# 464421_22-01_Power.net
KiCad netlist of a schematic drawn in Altium Designer
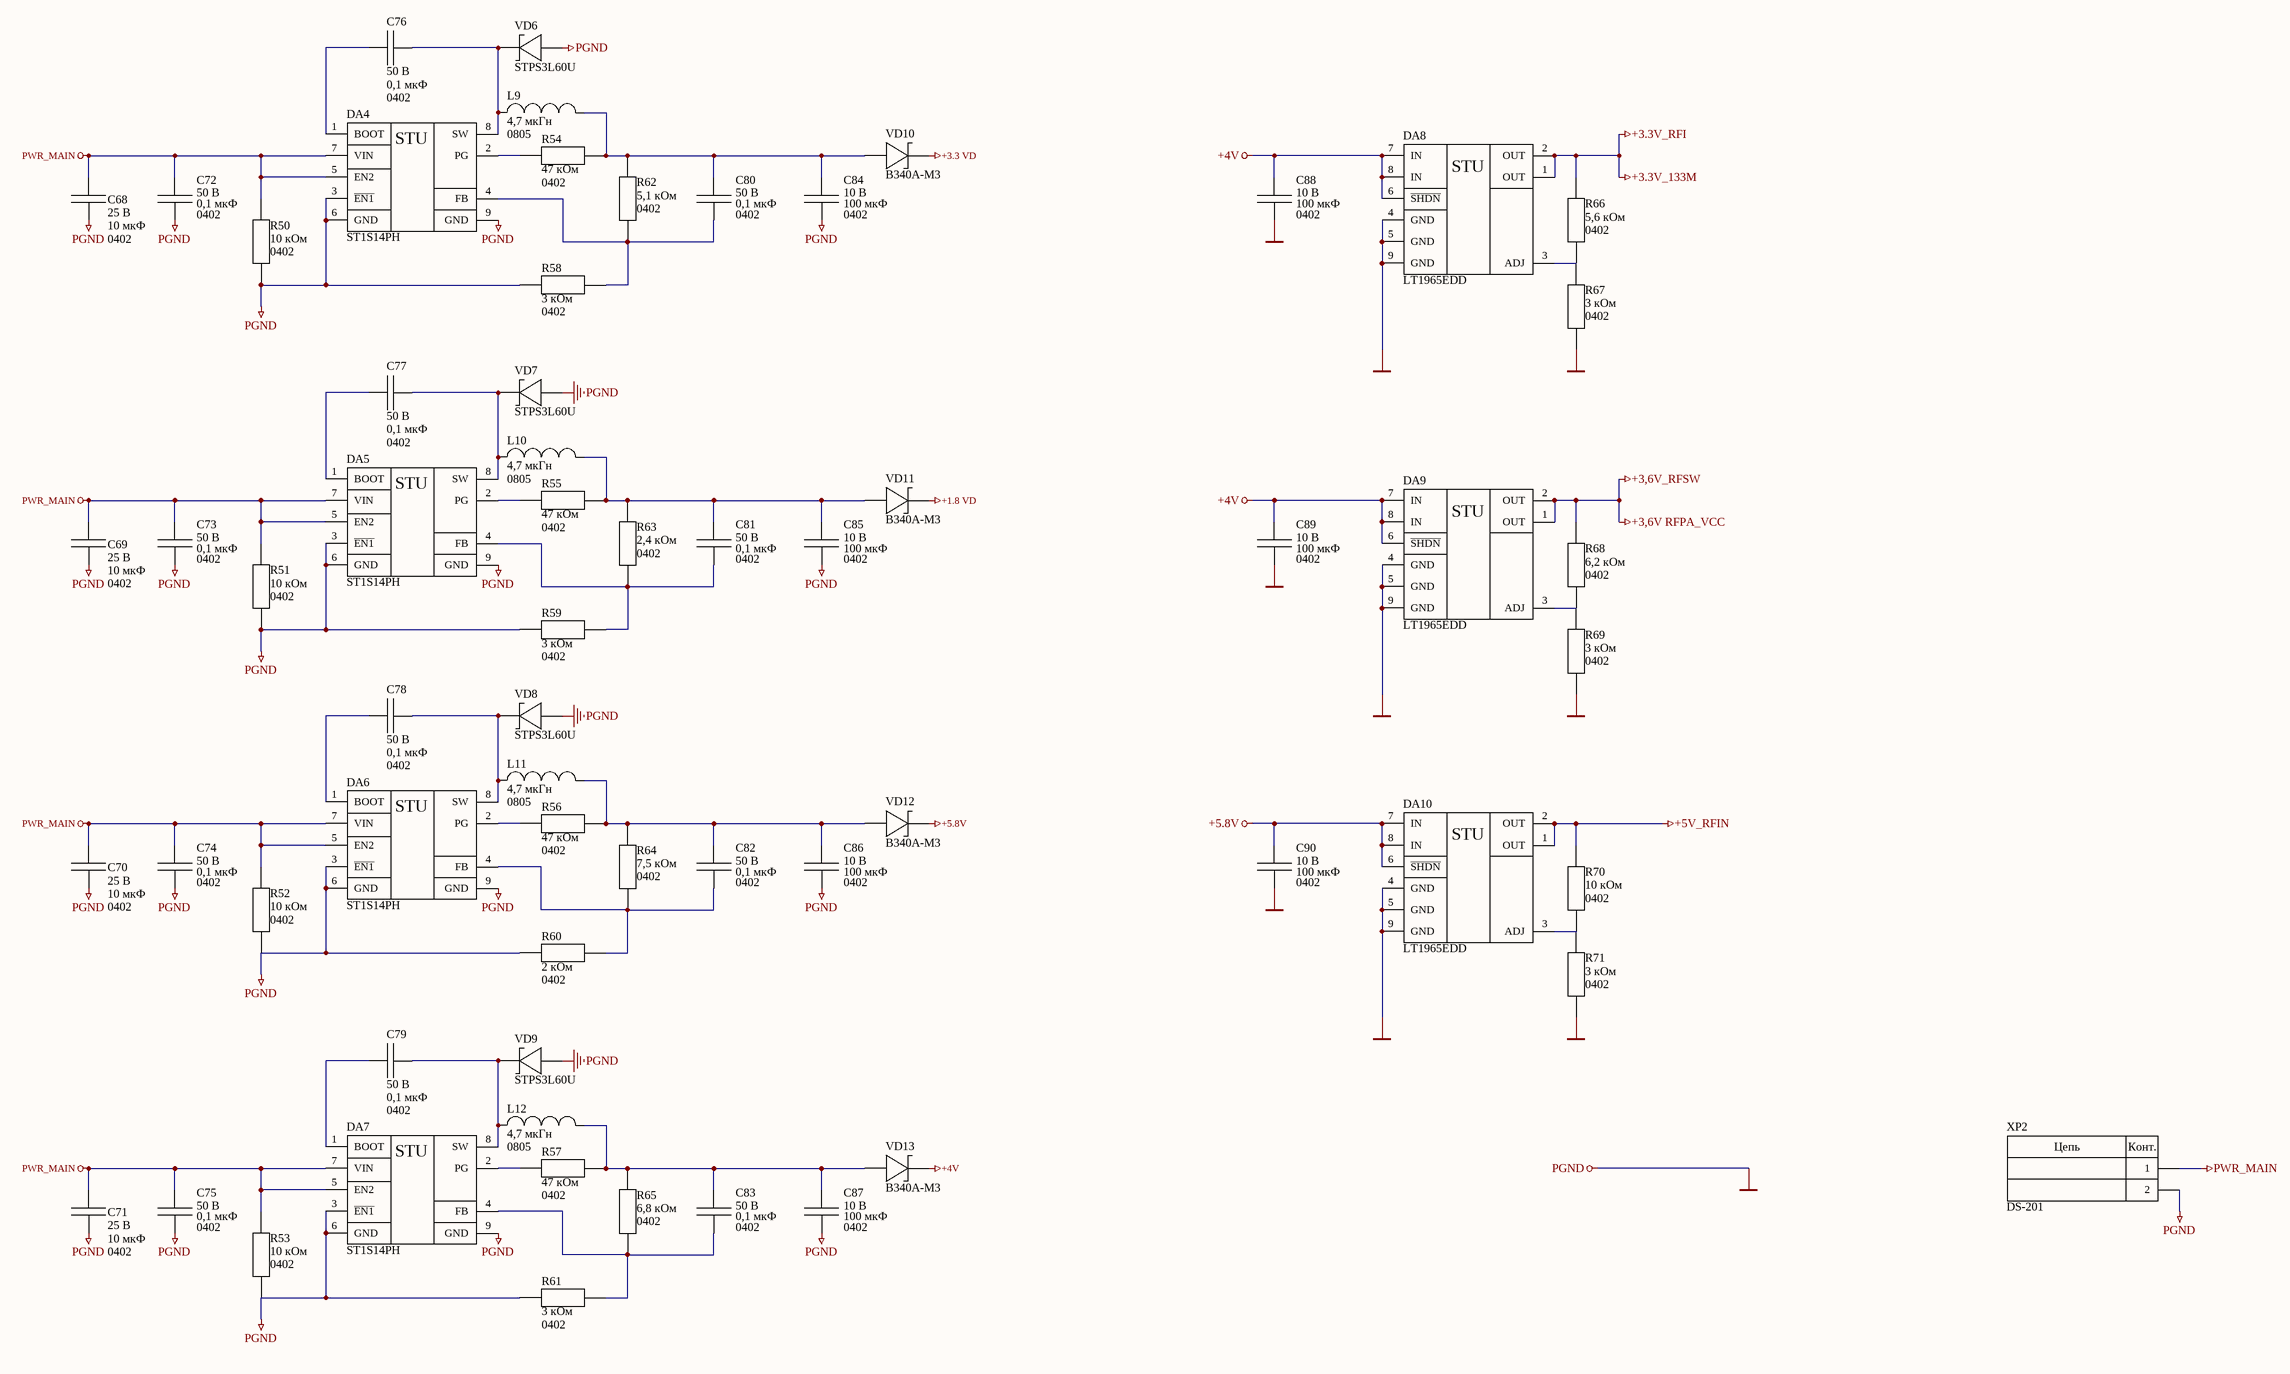
[diagram p0: МПСУ.464421.22-01 Power.SchDoc]

(export (version "E")
  (design (tool "Eeschema 10.0.6"))
  (components
    (comp (ref "C68")
      (value "10 мкФ")
      (footprint "Passive_V2_0:CAPC100X50X55L20N")
      (description "Capacitor 0402")
      (fields
        (field (name "PARTNUMBER") "GRM188R61E106KA73J")
        (field (name "MANUFACTURER") "Murata")
        (field (name "PEAK_CONDITION") "25 В")
        (field (name "PACKAGE") "0402")
        (field (name "DESIGNER") "Свидерский")
      )
      (libsource (lib "Passive_V2_0") (part "C 0402"))
    )
    (comp (ref "C69")
      (value "10 мкФ")
      (footprint "Passive_V2_0:CAPC100X50X55L20N")
      (description "Capacitor 0402")
      (fields
        (field (name "PARTNUMBER") "GRM188R61E106KA73J")
        (field (name "MANUFACTURER") "Murata")
        (field (name "PEAK_CONDITION") "25 В")
        (field (name "PACKAGE") "0402")
        (field (name "DESIGNER") "Свидерский")
      )
      (libsource (lib "Passive_V2_0") (part "C 0402"))
    )
    (comp (ref "C70")
      (value "10 мкФ")
      (footprint "Passive_V2_0:CAPC100X50X55L20N")
      (description "Capacitor 0402")
      (fields
        (field (name "PARTNUMBER") "GRM188R61E106KA73J")
        (field (name "MANUFACTURER") "Murata")
        (field (name "PEAK_CONDITION") "25 В")
        (field (name "PACKAGE") "0402")
        (field (name "DESIGNER") "Свидерский")
      )
      (libsource (lib "Passive_V2_0") (part "C 0402"))
    )
    (comp (ref "C71")
      (value "10 мкФ")
      (footprint "Passive_V2_0:CAPC100X50X55L20N")
      (description "Capacitor 0402")
      (fields
        (field (name "PARTNUMBER") "GRM188R61E106KA73J")
        (field (name "MANUFACTURER") "Murata")
        (field (name "PEAK_CONDITION") "25 В")
        (field (name "PACKAGE") "0402")
        (field (name "DESIGNER") "Свидерский")
      )
      (libsource (lib "Passive_V2_0") (part "C 0402"))
    )
    (comp (ref "C72")
      (value "0,1 мкФ")
      (footprint "Passive_V2_0:CAPC100X50X55L20N")
      (description "Capacitor 0402")
      (fields
        (field (name "PARTNUMBER") "GRM155R71H104KE14J")
        (field (name "MANUFACTURER") "Murata")
        (field (name "PEAK_CONDITION") "50 В")
        (field (name "PACKAGE") "0402")
        (field (name "DESIGNER") "Свидерский")
      )
      (libsource (lib "Passive_V2_0") (part "C 0402"))
    )
    (comp (ref "C73")
      (value "0,1 мкФ")
      (footprint "Passive_V2_0:CAPC100X50X55L20N")
      (description "Capacitor 0402")
      (fields
        (field (name "PARTNUMBER") "GRM155R71H104KE14J")
        (field (name "MANUFACTURER") "Murata")
        (field (name "PEAK_CONDITION") "50 В")
        (field (name "PACKAGE") "0402")
        (field (name "DESIGNER") "Свидерский")
      )
      (libsource (lib "Passive_V2_0") (part "C 0402"))
    )
    (comp (ref "C74")
      (value "0,1 мкФ")
      (footprint "Passive_V2_0:CAPC100X50X55L20N")
      (description "Capacitor 0402")
      (fields
        (field (name "PARTNUMBER") "GRM155R71H104KE14J")
        (field (name "MANUFACTURER") "Murata")
        (field (name "PEAK_CONDITION") "50 В")
        (field (name "PACKAGE") "0402")
        (field (name "DESIGNER") "Свидерский")
      )
      (libsource (lib "Passive_V2_0") (part "C 0402"))
    )
    (comp (ref "C75")
      (value "0,1 мкФ")
      (footprint "Passive_V2_0:CAPC100X50X55L20N")
      (description "Capacitor 0402")
      (fields
        (field (name "PARTNUMBER") "GRM155R71H104KE14J")
        (field (name "MANUFACTURER") "Murata")
        (field (name "PEAK_CONDITION") "50 В")
        (field (name "PACKAGE") "0402")
        (field (name "DESIGNER") "Свидерский")
      )
      (libsource (lib "Passive_V2_0") (part "C 0402"))
    )
    (comp (ref "C76")
      (value "0,1 мкФ")
      (footprint "Passive_V2_0:CAPC100X50X55L20N")
      (description "Capacitor 0402")
      (fields
        (field (name "PARTNUMBER") "GRM155R71H104KE14J")
        (field (name "MANUFACTURER") "Murata")
        (field (name "PEAK_CONDITION") "50 В")
        (field (name "PACKAGE") "0402")
        (field (name "DESIGNER") "Свидерский")
      )
      (libsource (lib "Passive_V2_0") (part "C 0402"))
    )
    (comp (ref "C77")
      (value "0,1 мкФ")
      (footprint "Passive_V2_0:CAPC100X50X55L20N")
      (description "Capacitor 0402")
      (fields
        (field (name "PARTNUMBER") "GRM155R71H104KE14J")
        (field (name "MANUFACTURER") "Murata")
        (field (name "PEAK_CONDITION") "50 В")
        (field (name "PACKAGE") "0402")
        (field (name "DESIGNER") "Свидерский")
      )
      (libsource (lib "Passive_V2_0") (part "C 0402"))
    )
    (comp (ref "C78")
      (value "0,1 мкФ")
      (footprint "Passive_V2_0:CAPC100X50X55L20N")
      (description "Capacitor 0402")
      (fields
        (field (name "PARTNUMBER") "GRM155R71H104KE14J")
        (field (name "MANUFACTURER") "Murata")
        (field (name "PEAK_CONDITION") "50 В")
        (field (name "PACKAGE") "0402")
        (field (name "DESIGNER") "Свидерский")
      )
      (libsource (lib "Passive_V2_0") (part "C 0402"))
    )
    (comp (ref "C79")
      (value "0,1 мкФ")
      (footprint "Passive_V2_0:CAPC100X50X55L20N")
      (description "Capacitor 0402")
      (fields
        (field (name "PARTNUMBER") "GRM155R71H104KE14J")
        (field (name "MANUFACTURER") "Murata")
        (field (name "PEAK_CONDITION") "50 В")
        (field (name "PACKAGE") "0402")
        (field (name "DESIGNER") "Свидерский")
      )
      (libsource (lib "Passive_V2_0") (part "C 0402"))
    )
    (comp (ref "C80")
      (value "0,1 мкФ")
      (footprint "Passive_V2_0:CAPC100X50X55L20N")
      (description "Capacitor 0402")
      (fields
        (field (name "PARTNUMBER") "GRM155R71H104KE14J")
        (field (name "MANUFACTURER") "Murata")
        (field (name "PEAK_CONDITION") "50 В")
        (field (name "PACKAGE") "0402")
        (field (name "DESIGNER") "Свидерский")
      )
      (libsource (lib "Passive_V2_0") (part "C 0402"))
    )
    (comp (ref "C81")
      (value "0,1 мкФ")
      (footprint "Passive_V2_0:CAPC100X50X55L20N")
      (description "Capacitor 0402")
      (fields
        (field (name "PARTNUMBER") "GRM155R71H104KE14J")
        (field (name "MANUFACTURER") "Murata")
        (field (name "PEAK_CONDITION") "50 В")
        (field (name "PACKAGE") "0402")
        (field (name "DESIGNER") "Свидерский")
      )
      (libsource (lib "Passive_V2_0") (part "C 0402"))
    )
    (comp (ref "C82")
      (value "0,1 мкФ")
      (footprint "Passive_V2_0:CAPC100X50X55L20N")
      (description "Capacitor 0402")
      (fields
        (field (name "PARTNUMBER") "GRM155R71H104KE14J")
        (field (name "MANUFACTURER") "Murata")
        (field (name "PEAK_CONDITION") "50 В")
        (field (name "PACKAGE") "0402")
        (field (name "DESIGNER") "Свидерский")
      )
      (libsource (lib "Passive_V2_0") (part "C 0402"))
    )
    (comp (ref "C83")
      (value "0,1 мкФ")
      (footprint "Passive_V2_0:CAPC100X50X55L20N")
      (description "Capacitor 0402")
      (fields
        (field (name "PARTNUMBER") "GRM155R71H104KE14J")
        (field (name "MANUFACTURER") "Murata")
        (field (name "PEAK_CONDITION") "50 В")
        (field (name "PACKAGE") "0402")
        (field (name "DESIGNER") "Свидерский")
      )
      (libsource (lib "Passive_V2_0") (part "C 0402"))
    )
    (comp (ref "C84")
      (value "100 мкФ")
      (footprint "Passive_V2_0:CAPC100X50X55L20N")
      (description "Capacitor 0402")
      (fields
        (field (name "PARTNUMBER") "C3216JB1A107M160AC")
        (field (name "MANUFACTURER") "TDK")
        (field (name "PEAK_CONDITION") "10 В")
        (field (name "PACKAGE") "0402")
        (field (name "DESIGNER") "Свидерский")
      )
      (libsource (lib "Passive_V2_0") (part "C 0402"))
    )
    (comp (ref "C85")
      (value "100 мкФ")
      (footprint "Passive_V2_0:CAPC100X50X55L20N")
      (description "Capacitor 0402")
      (fields
        (field (name "PARTNUMBER") "C3216JB1A107M160AC")
        (field (name "MANUFACTURER") "TDK")
        (field (name "PEAK_CONDITION") "10 В")
        (field (name "PACKAGE") "0402")
        (field (name "DESIGNER") "Свидерский")
      )
      (libsource (lib "Passive_V2_0") (part "C 0402"))
    )
    (comp (ref "C86")
      (value "100 мкФ")
      (footprint "Passive_V2_0:CAPC100X50X55L20N")
      (description "Capacitor 0402")
      (fields
        (field (name "PARTNUMBER") "C3216JB1A107M160AC")
        (field (name "MANUFACTURER") "TDK")
        (field (name "PEAK_CONDITION") "10 В")
        (field (name "PACKAGE") "0402")
        (field (name "DESIGNER") "Свидерский")
      )
      (libsource (lib "Passive_V2_0") (part "C 0402"))
    )
    (comp (ref "C87")
      (value "100 мкФ")
      (footprint "Passive_V2_0:CAPC100X50X55L20N")
      (description "Capacitor 0402")
      (fields
        (field (name "PARTNUMBER") "C3216JB1A107M160AC")
        (field (name "MANUFACTURER") "TDK")
        (field (name "PEAK_CONDITION") "10 В")
        (field (name "PACKAGE") "0402")
        (field (name "DESIGNER") "Свидерский")
      )
      (libsource (lib "Passive_V2_0") (part "C 0402"))
    )
    (comp (ref "C88")
      (value "100 мкФ")
      (footprint "Passive_V2_0:CAPC100X50X55L20N")
      (description "Capacitor 0402")
      (fields
        (field (name "PARTNUMBER") "C3216JB1A107M160AC")
        (field (name "MANUFACTURER") "TDK")
        (field (name "PEAK_CONDITION") "10 В")
        (field (name "PACKAGE") "0402")
        (field (name "DESIGNER") "Свидерский")
      )
      (libsource (lib "Passive_V2_0") (part "C 0402"))
    )
    (comp (ref "C89")
      (value "100 мкФ")
      (footprint "Passive_V2_0:CAPC100X50X55L20N")
      (description "Capacitor 0402")
      (fields
        (field (name "PARTNUMBER") "C3216JB1A107M160AC")
        (field (name "MANUFACTURER") "TDK")
        (field (name "PEAK_CONDITION") "10 В")
        (field (name "PACKAGE") "0402")
        (field (name "DESIGNER") "Свидерский")
      )
      (libsource (lib "Passive_V2_0") (part "C 0402"))
    )
    (comp (ref "C90")
      (value "100 мкФ")
      (footprint "Passive_V2_0:CAPC100X50X55L20N")
      (description "Capacitor 0402")
      (fields
        (field (name "PARTNUMBER") "C3216JB1A107M160AC")
        (field (name "MANUFACTURER") "TDK")
        (field (name "PEAK_CONDITION") "10 В")
        (field (name "PACKAGE") "0402")
        (field (name "DESIGNER") "Свидерский")
      )
      (libsource (lib "Passive_V2_0") (part "C 0402"))
    )
    (comp (ref "DA4")
      (value "ST1S14PH")
      (footprint "IC_V2_0:SOP127P600X175_HS-9N")
      (description "Up to 3 A step-down switching regulator")
      (fields
        (field (name "MANUFACTURER") "STMicroelectronics")
        (field (name "PARTNUMBER") "ST1S14PH")
        (field (name "DESIGNER") "Затонская")
      )
      (libsource (lib "IC_V2_0") (part "ST1S14PH"))
    )
    (comp (ref "DA5")
      (value "ST1S14PH")
      (footprint "IC_V2_0:SOP127P600X175_HS-9N")
      (description "Up to 3 A step-down switching regulator")
      (fields
        (field (name "MANUFACTURER") "STMicroelectronics")
        (field (name "PARTNUMBER") "ST1S14PH")
        (field (name "DESIGNER") "Затонская")
      )
      (libsource (lib "IC_V2_0") (part "ST1S14PH"))
    )
    (comp (ref "DA6")
      (value "ST1S14PH")
      (footprint "IC_V2_0:SOP127P600X175_HS-9N")
      (description "Up to 3 A step-down switching regulator")
      (fields
        (field (name "MANUFACTURER") "STMicroelectronics")
        (field (name "PARTNUMBER") "ST1S14PH")
        (field (name "DESIGNER") "Затонская")
      )
      (libsource (lib "IC_V2_0") (part "ST1S14PH"))
    )
    (comp (ref "DA7")
      (value "ST1S14PH")
      (footprint "IC_V2_0:SOP127P600X175_HS-9N")
      (description "Up to 3 A step-down switching regulator")
      (fields
        (field (name "MANUFACTURER") "STMicroelectronics")
        (field (name "PARTNUMBER") "ST1S14PH")
        (field (name "DESIGNER") "Затонская")
      )
      (libsource (lib "IC_V2_0") (part "ST1S14PH"))
    )
    (comp (ref "DA8")
      (value "LT1965EDD")
      (footprint "IC_V2_0:SON9P50_300X300X80L40X25T244X160N")
      (description "1.1A, Low Noise,  Low Dropout Linear Regulator")
      (fields
        (field (name "MANUFACTURER") "Analog Devices")
        (field (name "PARTNUMBER") "LT1965EDD")
        (field (name "DESIGNER") "Свидерский")
      )
      (libsource (lib "IC_V2_0") (part "LT1965*DD"))
    )
    (comp (ref "DA9")
      (value "LT1965EDD")
      (footprint "IC_V2_0:SON9P50_300X300X80L40X25T244X160N")
      (description "1.1A, Low Noise,  Low Dropout Linear Regulator")
      (fields
        (field (name "MANUFACTURER") "Analog Devices")
        (field (name "PARTNUMBER") "LT1965EDD")
        (field (name "DESIGNER") "Свидерский")
      )
      (libsource (lib "IC_V2_0") (part "LT1965*DD"))
    )
    (comp (ref "DA10")
      (value "LT1965EDD")
      (footprint "IC_V2_0:SON9P50_300X300X80L40X25T244X160N")
      (description "1.1A, Low Noise,  Low Dropout Linear Regulator")
      (fields
        (field (name "MANUFACTURER") "Analog Devices")
        (field (name "PARTNUMBER") "LT1965EDD")
        (field (name "DESIGNER") "Свидерский")
      )
      (libsource (lib "IC_V2_0") (part "LT1965*DD"))
    )
    (comp (ref "L9")
      (value "4,7 мкГн")
      (footprint "Passive_V2_0:INDC200X120X110L50N")
      (description "Inductor 0805")
      (fields
        (field (name "PARTNUMBER") "LQM21PZ4R7NGRD")
        (field (name "TOLERANCE") "30 %")
        (field (name "PACKAGE") "0805")
        (field (name "DESIGNER") "Свидерский")
      )
      (libsource (lib "Passive_V2_0") (part "L 0805"))
    )
    (comp (ref "L10")
      (value "4,7 мкГн")
      (footprint "Passive_V2_0:INDC200X120X110L50N")
      (description "Inductor 0805")
      (fields
        (field (name "PARTNUMBER") "LQM21PZ4R7NGRD")
        (field (name "TOLERANCE") "30 %")
        (field (name "PACKAGE") "0805")
        (field (name "DESIGNER") "Свидерский")
      )
      (libsource (lib "Passive_V2_0") (part "L 0805"))
    )
    (comp (ref "L11")
      (value "4,7 мкГн")
      (footprint "Passive_V2_0:INDC200X120X110L50N")
      (description "Inductor 0805")
      (fields
        (field (name "PARTNUMBER") "LQM21PZ4R7NGRD")
        (field (name "TOLERANCE") "30 %")
        (field (name "PACKAGE") "0805")
        (field (name "DESIGNER") "Свидерский")
      )
      (libsource (lib "Passive_V2_0") (part "L 0805"))
    )
    (comp (ref "L12")
      (value "4,7 мкГн")
      (footprint "Passive_V2_0:INDC200X120X110L50N")
      (description "Inductor 0805")
      (fields
        (field (name "PARTNUMBER") "LQM21PZ4R7NGRD")
        (field (name "TOLERANCE") "30 %")
        (field (name "PACKAGE") "0805")
        (field (name "DESIGNER") "Свидерский")
      )
      (libsource (lib "Passive_V2_0") (part "L 0805"))
    )
    (comp (ref "R50")
      (value "10 кОм")
      (footprint "Passive_V2_0:RESC100X50X40L25N")
      (description "Resistor 0402")
      (fields
        (field (name "PARTNUMBER") "RI0402L103JT")
        (field (name "TOLERANCE") "5 %")
        (field (name "PACKAGE") "0402")
        (field (name "DESIGNER") "Свидерский")
      )
      (libsource (lib "Passive_V2_0") (part "R 0402"))
    )
    (comp (ref "R51")
      (value "10 кОм")
      (footprint "Passive_V2_0:RESC100X50X40L25N")
      (description "Resistor 0402")
      (fields
        (field (name "PARTNUMBER") "RI0402L103JT")
        (field (name "TOLERANCE") "5 %")
        (field (name "PACKAGE") "0402")
        (field (name "DESIGNER") "Свидерский")
      )
      (libsource (lib "Passive_V2_0") (part "R 0402"))
    )
    (comp (ref "R52")
      (value "10 кОм")
      (footprint "Passive_V2_0:RESC100X50X40L25N")
      (description "Resistor 0402")
      (fields
        (field (name "PARTNUMBER") "RI0402L103JT")
        (field (name "TOLERANCE") "5 %")
        (field (name "PACKAGE") "0402")
        (field (name "DESIGNER") "Свидерский")
      )
      (libsource (lib "Passive_V2_0") (part "R 0402"))
    )
    (comp (ref "R53")
      (value "10 кОм")
      (footprint "Passive_V2_0:RESC100X50X40L25N")
      (description "Resistor 0402")
      (fields
        (field (name "PARTNUMBER") "RI0402L103JT")
        (field (name "TOLERANCE") "5 %")
        (field (name "PACKAGE") "0402")
        (field (name "DESIGNER") "Свидерский")
      )
      (libsource (lib "Passive_V2_0") (part "R 0402"))
    )
    (comp (ref "R54")
      (value "47 кОм")
      (footprint "Passive_V2_0:RESC100X50X40L25N")
      (description "Resistor 0402")
      (fields
        (field (name "PARTNUMBER") "RI0402L473JT")
        (field (name "TOLERANCE") "5 %")
        (field (name "PACKAGE") "0402")
        (field (name "DESIGNER") "Свидерский")
      )
      (libsource (lib "") (part "R 0402_1"))
    )
    (comp (ref "R55")
      (value "47 кОм")
      (footprint "Passive_V2_0:RESC100X50X40L25N")
      (description "Resistor 0402")
      (fields
        (field (name "PARTNUMBER") "RI0402L473JT")
        (field (name "TOLERANCE") "5 %")
        (field (name "PACKAGE") "0402")
        (field (name "DESIGNER") "Свидерский")
      )
      (libsource (lib "") (part "R 0402_1"))
    )
    (comp (ref "R56")
      (value "47 кОм")
      (footprint "Passive_V2_0:RESC100X50X40L25N")
      (description "Resistor 0402")
      (fields
        (field (name "PARTNUMBER") "RI0402L473JT")
        (field (name "TOLERANCE") "5 %")
        (field (name "PACKAGE") "0402")
        (field (name "DESIGNER") "Свидерский")
      )
      (libsource (lib "") (part "R 0402_1"))
    )
    (comp (ref "R57")
      (value "47 кОм")
      (footprint "Passive_V2_0:RESC100X50X40L25N")
      (description "Resistor 0402")
      (fields
        (field (name "PARTNUMBER") "RI0402L473JT")
        (field (name "TOLERANCE") "5 %")
        (field (name "PACKAGE") "0402")
        (field (name "DESIGNER") "Свидерский")
      )
      (libsource (lib "") (part "R 0402_1"))
    )
    (comp (ref "R58")
      (value "3 кОм")
      (footprint "Passive_V2_0:RESC100X50X40L25N")
      (description "Resistor 0402")
      (fields
        (field (name "PARTNUMBER") "RC0402FR-073KL")
        (field (name "TOLERANCE") "1 %")
        (field (name "PACKAGE") "0402")
        (field (name "DESIGNER") "Свидерский")
      )
      (libsource (lib "") (part "R 0402_2"))
    )
    (comp (ref "R59")
      (value "3 кОм")
      (footprint "Passive_V2_0:RESC100X50X40L25N")
      (description "Resistor 0402")
      (fields
        (field (name "PARTNUMBER") "RC0402FR-073KL")
        (field (name "TOLERANCE") "1 %")
        (field (name "PACKAGE") "0402")
        (field (name "DESIGNER") "Свидерский")
      )
      (libsource (lib "") (part "R 0402_2"))
    )
    (comp (ref "R60")
      (value "2 кОм")
      (footprint "Passive_V2_0:RESC100X50X40L25N")
      (description "Resistor 0402")
      (fields
        (field (name "PARTNUMBER") "RC-02W202JT")
        (field (name "TOLERANCE") "5 %")
        (field (name "PACKAGE") "0402")
        (field (name "DESIGNER") "Свидерский")
      )
      (libsource (lib "") (part "R 0402_2"))
    )
    (comp (ref "R61")
      (value "3 кОм")
      (footprint "Passive_V2_0:RESC100X50X40L25N")
      (description "Resistor 0402")
      (fields
        (field (name "PARTNUMBER") "RC0402FR-073KL")
        (field (name "TOLERANCE") "1 %")
        (field (name "PACKAGE") "0402")
        (field (name "DESIGNER") "Свидерский")
      )
      (libsource (lib "") (part "R 0402_2"))
    )
    (comp (ref "R62")
      (value "5,1 кОм")
      (footprint "Passive_V2_0:RESC100X50X40L25N")
      (description "Resistor 0402")
      (fields
        (field (name "PARTNUMBER") "RI0402L5101FT")
        (field (name "TOLERANCE") "1 %")
        (field (name "PACKAGE") "0402")
        (field (name "DESIGNER") "Свидерский")
      )
      (libsource (lib "Passive_V2_0") (part "R 0402"))
    )
    (comp (ref "R63")
      (value "2,4 кОм")
      (footprint "Passive_V2_0:RESC100X50X40L25N")
      (description "Resistor 0402")
      (fields
        (field (name "PARTNUMBER") "RC0402FR-072K4L")
        (field (name "TOLERANCE") "1 %")
        (field (name "PACKAGE") "0402")
        (field (name "DESIGNER") "Свидерский")
      )
      (libsource (lib "Passive_V2_0") (part "R 0402"))
    )
    (comp (ref "R64")
      (value "7,5 кОм")
      (footprint "Passive_V2_0:RESC100X50X40L25N")
      (description "Resistor 0402")
      (fields
        (field (name "PARTNUMBER") "RI0402L7501FT")
        (field (name "TOLERANCE") "1 %")
        (field (name "PACKAGE") "0402")
        (field (name "DESIGNER") "Свидерский")
      )
      (libsource (lib "Passive_V2_0") (part "R 0402"))
    )
    (comp (ref "R65")
      (value "6,8 кОм")
      (footprint "Passive_V2_0:RESC100X50X40L25N")
      (description "Resistor 0402")
      (fields
        (field (name "PARTNUMBER") "RC-02W682JT")
        (field (name "TOLERANCE") "5 %")
        (field (name "PACKAGE") "0402")
        (field (name "DESIGNER") "Свидерский")
      )
      (libsource (lib "Passive_V2_0") (part "R 0402"))
    )
    (comp (ref "R66")
      (value "5,6 кОм")
      (footprint "Passive_V2_0:RESC100X50X40L25N")
      (description "Resistor 0402")
      (fields
        (field (name "PARTNUMBER") "RI0402L5601FT")
        (field (name "TOLERANCE") "1 %")
        (field (name "PACKAGE") "0402")
        (field (name "DESIGNER") "Свидерский")
      )
      (libsource (lib "Passive_V2_0") (part "R 0402"))
    )
    (comp (ref "R67")
      (value "3 кОм")
      (footprint "Passive_V2_0:RESC100X50X40L25N")
      (description "Resistor 0402")
      (fields
        (field (name "PARTNUMBER") "RC0402FR-073KL")
        (field (name "TOLERANCE") "1 %")
        (field (name "PACKAGE") "0402")
        (field (name "DESIGNER") "Свидерский")
      )
      (libsource (lib "Passive_V2_0") (part "R 0402"))
    )
    (comp (ref "R68")
      (value "6,2 кОм")
      (footprint "Passive_V2_0:RESC100X50X40L25N")
      (description "Resistor 0402")
      (fields
        (field (name "PARTNUMBER") "RI0402L622JT")
        (field (name "TOLERANCE") "5 %")
        (field (name "PACKAGE") "0402")
        (field (name "DESIGNER") "Свидерский")
      )
      (libsource (lib "Passive_V2_0") (part "R 0402"))
    )
    (comp (ref "R69")
      (value "3 кОм")
      (footprint "Passive_V2_0:RESC100X50X40L25N")
      (description "Resistor 0402")
      (fields
        (field (name "PARTNUMBER") "RC0402FR-073KL")
        (field (name "TOLERANCE") "1 %")
        (field (name "PACKAGE") "0402")
        (field (name "DESIGNER") "Свидерский")
      )
      (libsource (lib "Passive_V2_0") (part "R 0402"))
    )
    (comp (ref "R70")
      (value "10 кОм")
      (footprint "Passive_V2_0:RESC100X50X40L25N")
      (description "Resistor 0402")
      (fields
        (field (name "PARTNUMBER") "RI0402L103JT")
        (field (name "TOLERANCE") "5 %")
        (field (name "PACKAGE") "0402")
        (field (name "DESIGNER") "Свидерский")
      )
      (libsource (lib "Passive_V2_0") (part "R 0402"))
    )
    (comp (ref "R71")
      (value "3 кОм")
      (footprint "Passive_V2_0:RESC100X50X40L25N")
      (description "Resistor 0402")
      (fields
        (field (name "PARTNUMBER") "RC0402FR-073KL")
        (field (name "TOLERANCE") "1 %")
        (field (name "PACKAGE") "0402")
        (field (name "DESIGNER") "Свидерский")
      )
      (libsource (lib "Passive_V2_0") (part "R 0402"))
    )
    (comp (ref "VD6")
      (value "STPS3L60U")
      (footprint "Discrete_V2_0:DIOM5436X11N")
      (description "60 V, 3 A low drop Schottky rectifier")
      (fields
        (field (name "MANUFACTURER") "Diodes Incorporated")
        (field (name "PARTNUMBER") "STPS3L60U")
        (field (name "DESIGNER") "Затонская")
      )
      (libsource (lib "Discrete_V2_0") (part "STPS3L60"))
    )
    (comp (ref "VD7")
      (value "STPS3L60U")
      (footprint "Discrete_V2_0:DIOM5436X11N")
      (description "60 V, 3 A low drop Schottky rectifier")
      (fields
        (field (name "MANUFACTURER") "Diodes Incorporated")
        (field (name "PARTNUMBER") "STPS3L60U")
        (field (name "DESIGNER") "Затонская")
      )
      (libsource (lib "Discrete_V2_0") (part "STPS3L60"))
    )
    (comp (ref "VD8")
      (value "STPS3L60U")
      (footprint "Discrete_V2_0:DIOM5436X11N")
      (description "60 V, 3 A low drop Schottky rectifier")
      (fields
        (field (name "MANUFACTURER") "Diodes Incorporated")
        (field (name "PARTNUMBER") "STPS3L60U")
        (field (name "DESIGNER") "Затонская")
      )
      (libsource (lib "Discrete_V2_0") (part "STPS3L60"))
    )
    (comp (ref "VD9")
      (value "STPS3L60U")
      (footprint "Discrete_V2_0:DIOM5436X11N")
      (description "60 V, 3 A low drop Schottky rectifier")
      (fields
        (field (name "MANUFACTURER") "Diodes Incorporated")
        (field (name "PARTNUMBER") "STPS3L60U")
        (field (name "DESIGNER") "Затонская")
      )
      (libsource (lib "Discrete_V2_0") (part "STPS3L60"))
    )
    (comp (ref "VD10")
      (value "B340A-M3")
      (footprint "Discrete_V2_0:DIOC4227X10N")
      (description "SURFACE MOUNT SCHOTTKY BARRIER RECTIFIER")
      (fields
        (field (name "MANUFACTURER") "Diodes Incorporated")
        (field (name "PARTNUMBER") "B340A-M3")
        (field (name "DESIGNER") "Затонская")
      )
      (libsource (lib "Discrete_V2_0") (part "B340A-M3"))
    )
    (comp (ref "VD11")
      (value "B340A-M3")
      (footprint "Discrete_V2_0:DIOC4227X10N")
      (description "SURFACE MOUNT SCHOTTKY BARRIER RECTIFIER")
      (fields
        (field (name "MANUFACTURER") "Diodes Incorporated")
        (field (name "PARTNUMBER") "B340A-M3")
        (field (name "DESIGNER") "Затонская")
      )
      (libsource (lib "Discrete_V2_0") (part "B340A-M3"))
    )
    (comp (ref "VD12")
      (value "B340A-M3")
      (footprint "Discrete_V2_0:DIOC4227X10N")
      (description "SURFACE MOUNT SCHOTTKY BARRIER RECTIFIER")
      (fields
        (field (name "MANUFACTURER") "Diodes Incorporated")
        (field (name "PARTNUMBER") "B340A-M3")
        (field (name "DESIGNER") "Затонская")
      )
      (libsource (lib "Discrete_V2_0") (part "B340A-M3"))
    )
    (comp (ref "VD13")
      (value "B340A-M3")
      (footprint "Discrete_V2_0:DIOC4227X10N")
      (description "SURFACE MOUNT SCHOTTKY BARRIER RECTIFIER")
      (fields
        (field (name "MANUFACTURER") "Diodes Incorporated")
        (field (name "PARTNUMBER") "B340A-M3")
        (field (name "DESIGNER") "Затонская")
      )
      (libsource (lib "Discrete_V2_0") (part "B340A-M3"))
    )
    (comp (ref "XP2")
      (value "DS-201")
      (footprint "Connectors_V2_0:DS-201")
      (description "DC supply 2 PIN DC-005 2.1x5.5mm")
      (fields
        (field (name "MANUFACTURER") "AMASS")
        (field (name "PARTNUMBER") "DS-201")
        (field (name "DESIGNER") "Лазба")
      )
      (libsource (lib "Connectors_V2_0") (part "DS-201"))
    )
  )
  (nets
    (net (code "1") (name "+1.8 VD") (class "Default")
      (node (ref "VD11") (pin "1") (pinfunction "C_1") (pintype "passive"))
    )
    (net (code "2") (name "+3,6V RFPA_VCC") (class "Default")
      (node (ref "DA9") (pin "1") (pinfunction "OUT_1") (pintype "passive"))
      (node (ref "DA9") (pin "2") (pinfunction "OUT_2") (pintype "passive"))
      (node (ref "R68") (pin "1") (pinfunction "1_1") (pintype "passive"))
    )
    (net (code "3") (name "+3.3 VD") (class "Default")
      (node (ref "VD10") (pin "1") (pinfunction "C_1") (pintype "passive"))
    )
    (net (code "4") (name "+3.3V_133M") (class "Default")
      (node (ref "DA8") (pin "1") (pinfunction "OUT_1") (pintype "passive"))
      (node (ref "DA8") (pin "2") (pinfunction "OUT_2") (pintype "passive"))
      (node (ref "R66") (pin "1") (pinfunction "1_1") (pintype "passive"))
    )
    (net (code "5") (name "+4V") (class "Default")
      (node (ref "C88") (pin "1") (pinfunction "1_1") (pintype "passive"))
      (node (ref "C89") (pin "1") (pinfunction "1_1") (pintype "passive"))
      (node (ref "DA8") (pin "6") (pinfunction "~{SHDN}_6") (pintype "passive"))
      (node (ref "DA8") (pin "7") (pinfunction "IN_7") (pintype "passive"))
      (node (ref "DA8") (pin "8") (pinfunction "IN_8") (pintype "passive"))
      (node (ref "DA9") (pin "6") (pinfunction "~{SHDN}_6") (pintype "passive"))
      (node (ref "DA9") (pin "7") (pinfunction "IN_7") (pintype "passive"))
      (node (ref "DA9") (pin "8") (pinfunction "IN_8") (pintype "passive"))
      (node (ref "VD13") (pin "1") (pinfunction "C_1") (pintype "passive"))
    )
    (net (code "6") (name "+5.8V") (class "Default")
      (node (ref "C90") (pin "1") (pinfunction "1_1") (pintype "passive"))
      (node (ref "DA10") (pin "6") (pinfunction "~{SHDN}_6") (pintype "passive"))
      (node (ref "DA10") (pin "7") (pinfunction "IN_7") (pintype "passive"))
      (node (ref "DA10") (pin "8") (pinfunction "IN_8") (pintype "passive"))
      (node (ref "VD12") (pin "1") (pinfunction "C_1") (pintype "passive"))
    )
    (net (code "7") (name "+5V_RFIN") (class "Default")
      (node (ref "DA10") (pin "1") (pinfunction "OUT_1") (pintype "passive"))
      (node (ref "DA10") (pin "2") (pinfunction "OUT_2") (pintype "passive"))
      (node (ref "R70") (pin "1") (pinfunction "1_1") (pintype "passive"))
    )
    (net (code "9") (name "GND") (class "Default")
      (node (ref "C68") (pin "2") (pinfunction "2_2") (pintype "passive"))
      (node (ref "C69") (pin "2") (pinfunction "2_2") (pintype "passive"))
      (node (ref "C70") (pin "2") (pinfunction "2_2") (pintype "passive"))
      (node (ref "C71") (pin "2") (pinfunction "2_2") (pintype "passive"))
      (node (ref "C72") (pin "2") (pinfunction "2_2") (pintype "passive"))
      (node (ref "C73") (pin "2") (pinfunction "2_2") (pintype "passive"))
      (node (ref "C74") (pin "2") (pinfunction "2_2") (pintype "passive"))
      (node (ref "C75") (pin "2") (pinfunction "2_2") (pintype "passive"))
      (node (ref "C84") (pin "2") (pinfunction "2_2") (pintype "passive"))
      (node (ref "C85") (pin "2") (pinfunction "2_2") (pintype "passive"))
      (node (ref "C86") (pin "2") (pinfunction "2_2") (pintype "passive"))
      (node (ref "C87") (pin "2") (pinfunction "2_2") (pintype "passive"))
      (node (ref "C88") (pin "2") (pinfunction "2_2") (pintype "passive"))
      (node (ref "C89") (pin "2") (pinfunction "2_2") (pintype "passive"))
      (node (ref "C90") (pin "2") (pinfunction "2_2") (pintype "passive"))
      (node (ref "DA10") (pin "4") (pinfunction "GND_4") (pintype "passive"))
      (node (ref "DA10") (pin "5") (pinfunction "GND_5") (pintype "passive"))
      (node (ref "DA10") (pin "9") (pinfunction "GND_9") (pintype "passive"))
      (node (ref "DA4") (pin "3") (pinfunction "~{EN1}_3") (pintype "passive"))
      (node (ref "DA4") (pin "6") (pinfunction "GND_6") (pintype "passive"))
      (node (ref "DA4") (pin "9") (pinfunction "GND_9") (pintype "passive"))
      (node (ref "DA5") (pin "3") (pinfunction "~{EN1}_3") (pintype "passive"))
      (node (ref "DA5") (pin "6") (pinfunction "GND_6") (pintype "passive"))
      (node (ref "DA5") (pin "9") (pinfunction "GND_9") (pintype "passive"))
      (node (ref "DA6") (pin "3") (pinfunction "~{EN1}_3") (pintype "passive"))
      (node (ref "DA6") (pin "6") (pinfunction "GND_6") (pintype "passive"))
      (node (ref "DA6") (pin "9") (pinfunction "GND_9") (pintype "passive"))
      (node (ref "DA7") (pin "3") (pinfunction "~{EN1}_3") (pintype "passive"))
      (node (ref "DA7") (pin "6") (pinfunction "GND_6") (pintype "passive"))
      (node (ref "DA7") (pin "9") (pinfunction "GND_9") (pintype "passive"))
      (node (ref "DA8") (pin "4") (pinfunction "GND_4") (pintype "passive"))
      (node (ref "DA8") (pin "5") (pinfunction "GND_5") (pintype "passive"))
      (node (ref "DA8") (pin "9") (pinfunction "GND_9") (pintype "passive"))
      (node (ref "DA9") (pin "4") (pinfunction "GND_4") (pintype "passive"))
      (node (ref "DA9") (pin "5") (pinfunction "GND_5") (pintype "passive"))
      (node (ref "DA9") (pin "9") (pinfunction "GND_9") (pintype "passive"))
      (node (ref "R50") (pin "2") (pinfunction "2_2") (pintype "passive"))
      (node (ref "R51") (pin "2") (pinfunction "2_2") (pintype "passive"))
      (node (ref "R52") (pin "2") (pinfunction "2_2") (pintype "passive"))
      (node (ref "R53") (pin "2") (pinfunction "2_2") (pintype "passive"))
      (node (ref "R58") (pin "2") (pinfunction "2_2") (pintype "passive"))
      (node (ref "R59") (pin "2") (pinfunction "2_2") (pintype "passive"))
      (node (ref "R60") (pin "2") (pinfunction "2_2") (pintype "passive"))
      (node (ref "R61") (pin "2") (pinfunction "2_2") (pintype "passive"))
      (node (ref "R67") (pin "2") (pinfunction "2_2") (pintype "passive"))
      (node (ref "R69") (pin "2") (pinfunction "2_2") (pintype "passive"))
      (node (ref "R71") (pin "2") (pinfunction "2_2") (pintype "passive"))
      (node (ref "VD6") (pin "2") (pinfunction "A_2") (pintype "passive"))
      (node (ref "VD7") (pin "2") (pinfunction "A_2") (pintype "passive"))
      (node (ref "VD8") (pin "2") (pinfunction "A_2") (pintype "passive"))
      (node (ref "VD9") (pin "2") (pinfunction "A_2") (pintype "passive"))
      (node (ref "XP2") (pin "2") (pinfunction "2_2") (pintype "passive"))
    )
    (net (code "10") (name "Net-(DA4-BOOT)") (class "Default")
      (node (ref "C76") (pin "1") (pinfunction "1_1") (pintype "passive"))
      (node (ref "DA4") (pin "1") (pinfunction "BOOT_1") (pintype "passive"))
    )
    (net (code "11") (name "Net-(DA4-FB)") (class "Default")
      (node (ref "C80") (pin "2") (pinfunction "2_2") (pintype "passive"))
      (node (ref "DA4") (pin "4") (pinfunction "FB_4") (pintype "passive"))
      (node (ref "R58") (pin "1") (pinfunction "1_1") (pintype "passive"))
      (node (ref "R62") (pin "2") (pinfunction "2_2") (pintype "passive"))
    )
    (net (code "12") (name "Net-(DA4-PG)") (class "Default")
      (node (ref "DA4") (pin "2") (pinfunction "PG_2") (pintype "passive"))
      (node (ref "R54") (pin "1") (pinfunction "1_1") (pintype "passive"))
    )
    (net (code "13") (name "Net-(DA4-SW)") (class "Default")
      (node (ref "C76") (pin "2") (pinfunction "2_2") (pintype "passive"))
      (node (ref "DA4") (pin "8") (pinfunction "SW_8") (pintype "passive"))
      (node (ref "L9") (pin "1") (pinfunction "1_1") (pintype "passive"))
      (node (ref "VD6") (pin "1") (pinfunction "C_1") (pintype "passive"))
    )
    (net (code "14") (name "Net-(DA5-BOOT)") (class "Default")
      (node (ref "C77") (pin "1") (pinfunction "1_1") (pintype "passive"))
      (node (ref "DA5") (pin "1") (pinfunction "BOOT_1") (pintype "passive"))
    )
    (net (code "15") (name "Net-(DA5-FB)") (class "Default")
      (node (ref "C81") (pin "2") (pinfunction "2_2") (pintype "passive"))
      (node (ref "DA5") (pin "4") (pinfunction "FB_4") (pintype "passive"))
      (node (ref "R59") (pin "1") (pinfunction "1_1") (pintype "passive"))
      (node (ref "R63") (pin "2") (pinfunction "2_2") (pintype "passive"))
    )
    (net (code "16") (name "Net-(DA5-PG)") (class "Default")
      (node (ref "DA5") (pin "2") (pinfunction "PG_2") (pintype "passive"))
      (node (ref "R55") (pin "1") (pinfunction "1_1") (pintype "passive"))
    )
    (net (code "17") (name "Net-(DA5-SW)") (class "Default")
      (node (ref "C77") (pin "2") (pinfunction "2_2") (pintype "passive"))
      (node (ref "DA5") (pin "8") (pinfunction "SW_8") (pintype "passive"))
      (node (ref "L10") (pin "1") (pinfunction "1_1") (pintype "passive"))
      (node (ref "VD7") (pin "1") (pinfunction "C_1") (pintype "passive"))
    )
    (net (code "18") (name "Net-(DA6-BOOT)") (class "Default")
      (node (ref "C78") (pin "1") (pinfunction "1_1") (pintype "passive"))
      (node (ref "DA6") (pin "1") (pinfunction "BOOT_1") (pintype "passive"))
    )
    (net (code "19") (name "Net-(DA6-FB)") (class "Default")
      (node (ref "C82") (pin "2") (pinfunction "2_2") (pintype "passive"))
      (node (ref "DA6") (pin "4") (pinfunction "FB_4") (pintype "passive"))
      (node (ref "R60") (pin "1") (pinfunction "1_1") (pintype "passive"))
      (node (ref "R64") (pin "2") (pinfunction "2_2") (pintype "passive"))
    )
    (net (code "20") (name "Net-(DA6-PG)") (class "Default")
      (node (ref "DA6") (pin "2") (pinfunction "PG_2") (pintype "passive"))
      (node (ref "R56") (pin "1") (pinfunction "1_1") (pintype "passive"))
    )
    (net (code "21") (name "Net-(DA6-SW)") (class "Default")
      (node (ref "C78") (pin "2") (pinfunction "2_2") (pintype "passive"))
      (node (ref "DA6") (pin "8") (pinfunction "SW_8") (pintype "passive"))
      (node (ref "L11") (pin "1") (pinfunction "1_1") (pintype "passive"))
      (node (ref "VD8") (pin "1") (pinfunction "C_1") (pintype "passive"))
    )
    (net (code "22") (name "Net-(DA7-BOOT)") (class "Default")
      (node (ref "C79") (pin "1") (pinfunction "1_1") (pintype "passive"))
      (node (ref "DA7") (pin "1") (pinfunction "BOOT_1") (pintype "passive"))
    )
    (net (code "23") (name "Net-(DA7-FB)") (class "Default")
      (node (ref "C83") (pin "2") (pinfunction "2_2") (pintype "passive"))
      (node (ref "DA7") (pin "4") (pinfunction "FB_4") (pintype "passive"))
      (node (ref "R61") (pin "1") (pinfunction "1_1") (pintype "passive"))
      (node (ref "R65") (pin "2") (pinfunction "2_2") (pintype "passive"))
    )
    (net (code "24") (name "Net-(DA7-PG)") (class "Default")
      (node (ref "DA7") (pin "2") (pinfunction "PG_2") (pintype "passive"))
      (node (ref "R57") (pin "1") (pinfunction "1_1") (pintype "passive"))
    )
    (net (code "25") (name "Net-(DA7-SW)") (class "Default")
      (node (ref "C79") (pin "2") (pinfunction "2_2") (pintype "passive"))
      (node (ref "DA7") (pin "8") (pinfunction "SW_8") (pintype "passive"))
      (node (ref "L12") (pin "1") (pinfunction "1_1") (pintype "passive"))
      (node (ref "VD9") (pin "1") (pinfunction "C_1") (pintype "passive"))
    )
    (net (code "26") (name "Net-(DA8-ADJ)") (class "Default")
      (node (ref "DA8") (pin "3") (pinfunction "ADJ_3") (pintype "passive"))
      (node (ref "R66") (pin "2") (pinfunction "2_2") (pintype "passive"))
      (node (ref "R67") (pin "1") (pinfunction "1_1") (pintype "passive"))
    )
    (net (code "27") (name "Net-(DA9-ADJ)") (class "Default")
      (node (ref "DA9") (pin "3") (pinfunction "ADJ_3") (pintype "passive"))
      (node (ref "R68") (pin "2") (pinfunction "2_2") (pintype "passive"))
      (node (ref "R69") (pin "1") (pinfunction "1_1") (pintype "passive"))
    )
    (net (code "28") (name "Net-(DA10-ADJ)") (class "Default")
      (node (ref "DA10") (pin "3") (pinfunction "ADJ_3") (pintype "passive"))
      (node (ref "R70") (pin "2") (pinfunction "2_2") (pintype "passive"))
      (node (ref "R71") (pin "1") (pinfunction "1_1") (pintype "passive"))
    )
    (net (code "29") (name "Net-(VD10-A)") (class "Default")
      (node (ref "C80") (pin "1") (pinfunction "1_1") (pintype "passive"))
      (node (ref "C84") (pin "1") (pinfunction "1_1") (pintype "passive"))
      (node (ref "L9") (pin "2") (pinfunction "2_2") (pintype "passive"))
      (node (ref "R54") (pin "2") (pinfunction "2_2") (pintype "passive"))
      (node (ref "R62") (pin "1") (pinfunction "1_1") (pintype "passive"))
      (node (ref "VD10") (pin "2") (pinfunction "A_2") (pintype "passive"))
    )
    (net (code "30") (name "Net-(VD11-A)") (class "Default")
      (node (ref "C81") (pin "1") (pinfunction "1_1") (pintype "passive"))
      (node (ref "C85") (pin "1") (pinfunction "1_1") (pintype "passive"))
      (node (ref "L10") (pin "2") (pinfunction "2_2") (pintype "passive"))
      (node (ref "R55") (pin "2") (pinfunction "2_2") (pintype "passive"))
      (node (ref "R63") (pin "1") (pinfunction "1_1") (pintype "passive"))
      (node (ref "VD11") (pin "2") (pinfunction "A_2") (pintype "passive"))
    )
    (net (code "31") (name "Net-(VD12-A)") (class "Default")
      (node (ref "C82") (pin "1") (pinfunction "1_1") (pintype "passive"))
      (node (ref "C86") (pin "1") (pinfunction "1_1") (pintype "passive"))
      (node (ref "L11") (pin "2") (pinfunction "2_2") (pintype "passive"))
      (node (ref "R56") (pin "2") (pinfunction "2_2") (pintype "passive"))
      (node (ref "R64") (pin "1") (pinfunction "1_1") (pintype "passive"))
      (node (ref "VD12") (pin "2") (pinfunction "A_2") (pintype "passive"))
    )
    (net (code "32") (name "Net-(VD13-A)") (class "Default")
      (node (ref "C83") (pin "1") (pinfunction "1_1") (pintype "passive"))
      (node (ref "C87") (pin "1") (pinfunction "1_1") (pintype "passive"))
      (node (ref "L12") (pin "2") (pinfunction "2_2") (pintype "passive"))
      (node (ref "R57") (pin "2") (pinfunction "2_2") (pintype "passive"))
      (node (ref "R65") (pin "1") (pinfunction "1_1") (pintype "passive"))
      (node (ref "VD13") (pin "2") (pinfunction "A_2") (pintype "passive"))
    )
    (net (code "33") (name "PWR_MAIN") (class "Default")
      (node (ref "C68") (pin "1") (pinfunction "1_1") (pintype "passive"))
      (node (ref "C69") (pin "1") (pinfunction "1_1") (pintype "passive"))
      (node (ref "C70") (pin "1") (pinfunction "1_1") (pintype "passive"))
      (node (ref "C71") (pin "1") (pinfunction "1_1") (pintype "passive"))
      (node (ref "C72") (pin "1") (pinfunction "1_1") (pintype "passive"))
      (node (ref "C73") (pin "1") (pinfunction "1_1") (pintype "passive"))
      (node (ref "C74") (pin "1") (pinfunction "1_1") (pintype "passive"))
      (node (ref "C75") (pin "1") (pinfunction "1_1") (pintype "passive"))
      (node (ref "DA4") (pin "5") (pinfunction "EN2_5") (pintype "passive"))
      (node (ref "DA4") (pin "7") (pinfunction "VIN_7") (pintype "passive"))
      (node (ref "DA5") (pin "5") (pinfunction "EN2_5") (pintype "passive"))
      (node (ref "DA5") (pin "7") (pinfunction "VIN_7") (pintype "passive"))
      (node (ref "DA6") (pin "5") (pinfunction "EN2_5") (pintype "passive"))
      (node (ref "DA6") (pin "7") (pinfunction "VIN_7") (pintype "passive"))
      (node (ref "DA7") (pin "5") (pinfunction "EN2_5") (pintype "passive"))
      (node (ref "DA7") (pin "7") (pinfunction "VIN_7") (pintype "passive"))
      (node (ref "R50") (pin "1") (pinfunction "1_1") (pintype "passive"))
      (node (ref "R51") (pin "1") (pinfunction "1_1") (pintype "passive"))
      (node (ref "R52") (pin "1") (pinfunction "1_1") (pintype "passive"))
      (node (ref "R53") (pin "1") (pinfunction "1_1") (pintype "passive"))
      (node (ref "XP2") (pin "1") (pinfunction "1_1") (pintype "passive"))
    )
  )
)
